# Telemetry_I2C.net
KiCad netlist of a schematic drawn in Altium Designer
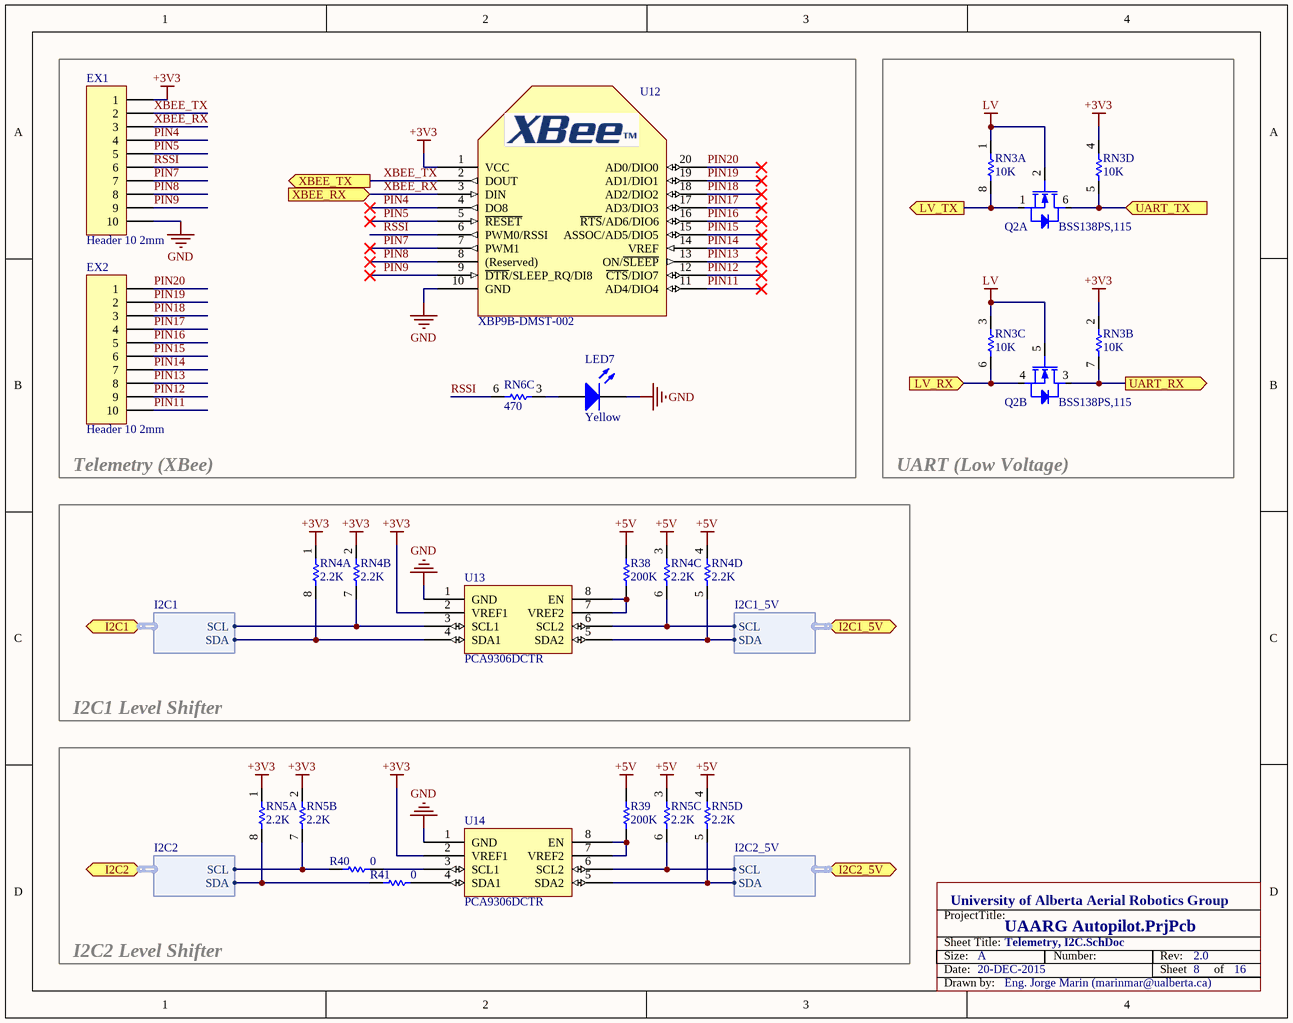
[diagram p0: Telemetry, I2C.SchDoc]

(export (version "E")
  (design (tool "Eeschema 10.0.6"))
  (components
    (comp (ref "EX1")
      (value "Header 10 2mm")
      (footprint "2mm pitch female header")
      (description "Header, 10-Pin")
      (fields
        (field (name "MANUFACTURER") "Sullins Connector Solutions")
        (field (name "MANUFACTURER PART NUMBER") "NPPN101BFCN-RC")
      )
      (libsource (lib "Miscellaneous Connectors") (part "Header 10"))
    )
    (comp (ref "EX2")
      (value "Header 10 2mm")
      (footprint "2mm pitch female header")
      (description "Header, 10-Pin")
      (fields
        (field (name "MANUFACTURER") "Sullins Connector Solutions")
        (field (name "MANUFACTURER PART NUMBER") "NPPN101BFCN-RC")
      )
      (libsource (lib "Miscellaneous Connectors") (part "Header 10"))
    )
    (comp (ref "LED7")
      (value "LED")
      (footprint "LED_0603[1608M]")
      (description "LED YELLOW CLEAR 0603 SMD")
      (fields
        (field (name "MANUFACTURER") "Lite-On Inc.")
        (field (name "MANUFACTURER PART NUMBER") "LTST-C190YKT")
        (field (name "COLOR") "Yellow")
      )
      (libsource (lib "UAARG Autopilot") (part "LED"))
    )
    (comp (ref "Q2")
      (value "N-CH MOSFET-D-ARRAY")
      (footprint "SOT363-6")
      (description "N-CH MOSFET W/ DIODE DUAL PACKAGE")
      (fields
        (field (name "MANUFACTURER PART NUMBER") "BSS138PS,115")
        (field (name "MANUFACTURER") "NXP Semiconductors")
      )
      (libsource (lib "UAARG Autopilot") (part "N-CH MOSFET-D-ARRAY"))
    )
    (comp (ref "R38")
      (value "200K")
      (footprint "RES_0402[1005M]")
      (description "Resistor")
      (fields
        (field (name "MANUFACTURER") "Yageo")
        (field (name "MANUFACTURER PART NUMBER") "RC0402FR-07200KL")
      )
      (libsource (lib "UAARG Autopilot") (part "RES"))
    )
    (comp (ref "R39")
      (value "200K")
      (footprint "RES_0402[1005M]")
      (description "Resistor")
      (fields
        (field (name "MANUFACTURER") "Yageo")
        (field (name "MANUFACTURER PART NUMBER") "RC0402FR-07200KL")
      )
      (libsource (lib "UAARG Autopilot") (part "RES"))
    )
    (comp (ref "R40")
      (value "0")
      (footprint "JUMPER_RES_0402")
      (description "Resistor")
      (fields
        (field (name "MANUFACTURER PART NUMBER") "RC0402JR-070RL")
        (field (name "MANUFACTURER") "Yageo")
      )
      (libsource (lib "UAARG Autopilot") (part "RES"))
    )
    (comp (ref "R41")
      (value "0")
      (footprint "JUMPER_RES_0402")
      (description "Resistor")
      (fields
        (field (name "MANUFACTURER PART NUMBER") "RC0402JR-070RL")
        (field (name "MANUFACTURER") "Yageo")
      )
      (libsource (lib "UAARG Autopilot") (part "RES"))
    )
    (comp (ref "RN3")
      (value "10K")
      (footprint "RES ARRAY SMD")
      (description "Isolated Resistor Network")
      (fields
        (field (name "MANUFACTURER PART NUMBER") "YC164-JR-0710KL")
        (field (name "MANUFACTURER") "Yageo")
      )
      (libsource (lib "UAARG Autopilot") (part "Res Network 1"))
    )
    (comp (ref "RN4")
      (value "2.2K")
      (footprint "RES ARRAY SMD")
      (description "Isolated Resistor Network")
      (fields
        (field (name "MANUFACTURER PART NUMBER") "YC164-JR-072K2L")
        (field (name "MANUFACTURER") "Yageo")
      )
      (libsource (lib "UAARG Autopilot") (part "Res Network 1"))
    )
    (comp (ref "RN5")
      (value "2.2K")
      (footprint "RES ARRAY SMD")
      (description "Isolated Resistor Network")
      (fields
        (field (name "MANUFACTURER PART NUMBER") "YC164-JR-072K2L")
        (field (name "MANUFACTURER") "Yageo")
      )
      (libsource (lib "UAARG Autopilot") (part "Res Network 1"))
    )
    (comp (ref "RN6")
      (value "470")
      (footprint "RES ARRAY SMD")
      (description "Isolated Resistor Network")
      (fields
        (field (name "MANUFACTURER") "Yageo")
        (field (name "MANUFACTURER PART NUMBER") "YC164-JR-07470RL")
      )
      (libsource (lib "UAARG Autopilot") (part "Res Network 1"))
    )
    (comp (ref "U12")
      (value "XBee / XBee PRO")
      (footprint "XBee PRO for headers")
      (description "MODULE XBEE PRO S3B 900HP RPSMA")
      (fields
        (field (name "MANUFACTURER") "Digi International")
        (field (name "MANUFACTURER PART NUMBER") "XBP9B-DMST-002")
      )
      (libsource (lib "UAARG Autopilot") (part "XBee / XBee PRO"))
    )
    (comp (ref "U13")
      (value "PCA9306DC")
      (footprint "DCT-8 (LSSOP-8)")
      (description "IC VOLT-LEVEL TRANSLATOR SM8")
      (fields
        (field (name "MANUFACTURER") "Texas Instruments")
        (field (name "MANUFACTURER PART NUMBER") "PCA9306DCTR")
      )
      (libsource (lib "UAARG Autopilot") (part "PCA9306DC"))
    )
    (comp (ref "U14")
      (value "PCA9306DC")
      (footprint "DCT-8 (LSSOP-8)")
      (description "IC VOLT-LEVEL TRANSLATOR SM8")
      (fields
        (field (name "MANUFACTURER") "Texas Instruments")
        (field (name "MANUFACTURER PART NUMBER") "PCA9306DCTR")
      )
      (libsource (lib "UAARG Autopilot") (part "PCA9306DC"))
    )
  )
  (nets
    (net (code "5") (name "+3V3") (class "Default")
      (node (ref "EX1") (pin "1") (pinfunction "1_1") (pintype "passive"))
      (node (ref "RN3") (pin "2") (pinfunction "2_2") (pintype "passive"))
      (node (ref "RN3") (pin "4") (pinfunction "4_4") (pintype "passive"))
      (node (ref "RN4") (pin "1") (pinfunction "1_1") (pintype "passive"))
      (node (ref "RN4") (pin "2") (pinfunction "2_2") (pintype "passive"))
      (node (ref "RN5") (pin "1") (pinfunction "1_1") (pintype "passive"))
      (node (ref "RN5") (pin "2") (pinfunction "2_2") (pintype "passive"))
      (node (ref "U12") (pin "1") (pinfunction "VCC_1") (pintype "power_in"))
      (node (ref "U13") (pin "2") (pinfunction "VREF1_2") (pintype "power_in"))
      (node (ref "U14") (pin "2") (pinfunction "VREF1_2") (pintype "power_in"))
    )
    (net (code "6") (name "+5V") (class "Default")
      (node (ref "R38") (pin "1") (pinfunction "1_1") (pintype "passive"))
      (node (ref "R39") (pin "1") (pinfunction "1_1") (pintype "passive"))
      (node (ref "RN4") (pin "3") (pinfunction "3_3") (pintype "passive"))
      (node (ref "RN4") (pin "4") (pinfunction "4_4") (pintype "passive"))
      (node (ref "RN5") (pin "3") (pinfunction "3_3") (pintype "passive"))
      (node (ref "RN5") (pin "4") (pinfunction "4_4") (pintype "passive"))
    )
    (net (code "7") (name "/LV_RX") (class "Default")
      (node (ref "Q2") (pin "4") (pinfunction "S2_4") (pintype "passive"))
      (node (ref "RN3") (pin "6") (pinfunction "6_6") (pintype "passive"))
    )
    (net (code "8") (name "/LV_TX") (class "Default")
      (node (ref "Q2") (pin "1") (pinfunction "S1_1") (pintype "passive"))
      (node (ref "RN3") (pin "8") (pinfunction "8_8") (pintype "passive"))
    )
    (net (code "9") (name "/PIN4") (class "Default")
      (node (ref "EX1") (pin "4") (pinfunction "4_4") (pintype "passive"))
      (node (ref "U12") (pin "4") (pinfunction "DO8_4") (pintype "output"))
    )
    (net (code "10") (name "/PIN5") (class "Default")
      (node (ref "EX1") (pin "5") (pinfunction "5_5") (pintype "passive"))
      (node (ref "U12") (pin "5") (pinfunction "~{RESET}_5") (pintype "input"))
    )
    (net (code "11") (name "/PIN7") (class "Default")
      (node (ref "EX1") (pin "7") (pinfunction "7_7") (pintype "passive"))
      (node (ref "U12") (pin "7") (pinfunction "PWM1_7") (pintype "output"))
    )
    (net (code "12") (name "/PIN8") (class "Default")
      (node (ref "EX1") (pin "8") (pinfunction "8_8") (pintype "passive"))
      (node (ref "U12") (pin "8") (pinfunction "(Reserved)_8") (pintype "passive"))
    )
    (net (code "13") (name "/PIN9") (class "Default")
      (node (ref "EX1") (pin "9") (pinfunction "9_9") (pintype "passive"))
      (node (ref "U12") (pin "9") (pinfunction "~{DTR}/SLEEP_RQ/DI8_9") (pintype "input"))
    )
    (net (code "14") (name "/PIN11") (class "Default")
      (node (ref "EX2") (pin "10") (pinfunction "10_10") (pintype "passive"))
      (node (ref "U12") (pin "11") (pinfunction "AD4/DIO4_11") (pintype "bidirectional"))
    )
    (net (code "15") (name "/PIN12") (class "Default")
      (node (ref "EX2") (pin "9") (pinfunction "9_9") (pintype "passive"))
      (node (ref "U12") (pin "12") (pinfunction "~{CTS}/DIO7_12") (pintype "bidirectional"))
    )
    (net (code "16") (name "/PIN13") (class "Default")
      (node (ref "EX2") (pin "8") (pinfunction "8_8") (pintype "passive"))
      (node (ref "U12") (pin "13") (pinfunction "ON/~{SLEEP}_13") (pintype "output"))
    )
    (net (code "17") (name "/PIN14") (class "Default")
      (node (ref "EX2") (pin "7") (pinfunction "7_7") (pintype "passive"))
      (node (ref "U12") (pin "14") (pinfunction "VREF_14") (pintype "input"))
    )
    (net (code "18") (name "/PIN15") (class "Default")
      (node (ref "EX2") (pin "6") (pinfunction "6_6") (pintype "passive"))
      (node (ref "U12") (pin "15") (pinfunction "ASSOC/AD5/DIO5_15") (pintype "bidirectional"))
    )
    (net (code "19") (name "/PIN16") (class "Default")
      (node (ref "EX2") (pin "5") (pinfunction "5_5") (pintype "passive"))
      (node (ref "U12") (pin "16") (pinfunction "~{RTS}/AD6/DIO6_16") (pintype "bidirectional"))
    )
    (net (code "20") (name "/PIN17") (class "Default")
      (node (ref "EX2") (pin "4") (pinfunction "4_4") (pintype "passive"))
      (node (ref "U12") (pin "17") (pinfunction "AD3/DIO3_17") (pintype "bidirectional"))
    )
    (net (code "21") (name "/PIN18") (class "Default")
      (node (ref "EX2") (pin "3") (pinfunction "3_3") (pintype "passive"))
      (node (ref "U12") (pin "18") (pinfunction "AD2/DIO2_18") (pintype "bidirectional"))
    )
    (net (code "22") (name "/PIN19") (class "Default")
      (node (ref "EX2") (pin "2") (pinfunction "2_2") (pintype "passive"))
      (node (ref "U12") (pin "19") (pinfunction "AD1/DIO1_19") (pintype "bidirectional"))
    )
    (net (code "23") (name "/PIN20") (class "Default")
      (node (ref "EX2") (pin "1") (pinfunction "1_1") (pintype "passive"))
      (node (ref "U12") (pin "20") (pinfunction "AD0/DIO0_20") (pintype "bidirectional"))
    )
    (net (code "24") (name "/RSSI") (class "Default")
      (node (ref "EX1") (pin "6") (pinfunction "6_6") (pintype "passive"))
      (node (ref "RN6") (pin "6") (pinfunction "6_6") (pintype "passive"))
      (node (ref "U12") (pin "6") (pinfunction "PWM0/RSSI_6") (pintype "output"))
    )
    (net (code "25") (name "/UART_RX") (class "Default")
      (node (ref "Q2") (pin "3") (pinfunction "D1_3") (pintype "passive"))
      (node (ref "RN3") (pin "7") (pinfunction "7_7") (pintype "passive"))
    )
    (net (code "26") (name "/UART_TX") (class "Default")
      (node (ref "Q2") (pin "6") (pinfunction "D1_6") (pintype "passive"))
      (node (ref "RN3") (pin "5") (pinfunction "5_5") (pintype "passive"))
    )
    (net (code "27") (name "/XBEE_RX") (class "Default")
      (node (ref "EX1") (pin "3") (pinfunction "3_3") (pintype "passive"))
      (node (ref "U12") (pin "3") (pinfunction "DIN_3") (pintype "input"))
    )
    (net (code "28") (name "/XBEE_TX") (class "Default")
      (node (ref "EX1") (pin "2") (pinfunction "2_2") (pintype "passive"))
      (node (ref "U12") (pin "2") (pinfunction "DOUT_2") (pintype "output"))
    )
    (net (code "33") (name "GND") (class "Default")
      (node (ref "EX1") (pin "10") (pinfunction "10_10") (pintype "passive"))
      (node (ref "LED7") (pin "2") (pinfunction "K_2") (pintype "passive"))
      (node (ref "U12") (pin "10") (pinfunction "GND_10") (pintype "power_in"))
      (node (ref "U13") (pin "1") (pinfunction "GND_1") (pintype "power_in"))
      (node (ref "U14") (pin "1") (pinfunction "GND_1") (pintype "power_in"))
    )
    (net (code "34") (name "LV") (class "Default")
      (node (ref "Q2") (pin "2") (pinfunction "G1_2") (pintype "passive"))
      (node (ref "Q2") (pin "5") (pinfunction "G2_5") (pintype "passive"))
      (node (ref "RN3") (pin "1") (pinfunction "1_1") (pintype "passive"))
      (node (ref "RN3") (pin "3") (pinfunction "3_3") (pintype "passive"))
    )
    (net (code "35") (name "Net-(LED7-A)") (class "Default")
      (node (ref "LED7") (pin "1") (pinfunction "A_1") (pintype "passive"))
      (node (ref "RN6") (pin "3") (pinfunction "3_3") (pintype "passive"))
    )
    (net (code "36") (name "Net-(R40-Pad2)") (class "Default")
      (node (ref "R40") (pin "2") (pinfunction "2_2") (pintype "passive"))
      (node (ref "RN5") (pin "7") (pinfunction "7_7") (pintype "passive"))
    )
    (net (code "37") (name "Net-(R41-Pad2)") (class "Default")
      (node (ref "R41") (pin "2") (pinfunction "2_2") (pintype "passive"))
      (node (ref "RN5") (pin "8") (pinfunction "8_8") (pintype "passive"))
    )
    (net (code "38") (name "Net-(U13-EN)") (class "Default")
      (node (ref "R38") (pin "2") (pinfunction "2_2") (pintype "passive"))
      (node (ref "U13") (pin "7") (pinfunction "VREF2_7") (pintype "power_in"))
      (node (ref "U13") (pin "8") (pinfunction "EN_8") (pintype "power_in"))
    )
    (net (code "39") (name "Net-(U13-SCL1)") (class "Default")
      (node (ref "RN4") (pin "7") (pinfunction "7_7") (pintype "passive"))
      (node (ref "U13") (pin "3") (pinfunction "SCL1_3") (pintype "bidirectional"))
    )
    (net (code "40") (name "Net-(U13-SCL2)") (class "Default")
      (node (ref "RN4") (pin "6") (pinfunction "6_6") (pintype "passive"))
      (node (ref "U13") (pin "6") (pinfunction "SCL2_6") (pintype "bidirectional"))
    )
    (net (code "41") (name "Net-(U13-SDA1)") (class "Default")
      (node (ref "RN4") (pin "8") (pinfunction "8_8") (pintype "passive"))
      (node (ref "U13") (pin "4") (pinfunction "SDA1_4") (pintype "bidirectional"))
    )
    (net (code "42") (name "Net-(U13-SDA2)") (class "Default")
      (node (ref "RN4") (pin "5") (pinfunction "5_5") (pintype "passive"))
      (node (ref "U13") (pin "5") (pinfunction "SDA2_5") (pintype "bidirectional"))
    )
    (net (code "43") (name "Net-(U14-EN)") (class "Default")
      (node (ref "R39") (pin "2") (pinfunction "2_2") (pintype "passive"))
      (node (ref "U14") (pin "7") (pinfunction "VREF2_7") (pintype "power_in"))
      (node (ref "U14") (pin "8") (pinfunction "EN_8") (pintype "power_in"))
    )
    (net (code "44") (name "Net-(U14-SCL1)") (class "Default")
      (node (ref "R40") (pin "1") (pinfunction "1_1") (pintype "passive"))
      (node (ref "U14") (pin "3") (pinfunction "SCL1_3") (pintype "bidirectional"))
    )
    (net (code "45") (name "Net-(U14-SCL2)") (class "Default")
      (node (ref "RN5") (pin "6") (pinfunction "6_6") (pintype "passive"))
      (node (ref "U14") (pin "6") (pinfunction "SCL2_6") (pintype "bidirectional"))
    )
    (net (code "46") (name "Net-(U14-SDA1)") (class "Default")
      (node (ref "R41") (pin "1") (pinfunction "1_1") (pintype "passive"))
      (node (ref "U14") (pin "4") (pinfunction "SDA1_4") (pintype "bidirectional"))
    )
    (net (code "47") (name "Net-(U14-SDA2)") (class "Default")
      (node (ref "RN5") (pin "5") (pinfunction "5_5") (pintype "passive"))
      (node (ref "U14") (pin "5") (pinfunction "SDA2_5") (pintype "bidirectional"))
    )
  )
)
